# Sheet1.net
KiCad netlist of a schematic drawn in Altium Designer
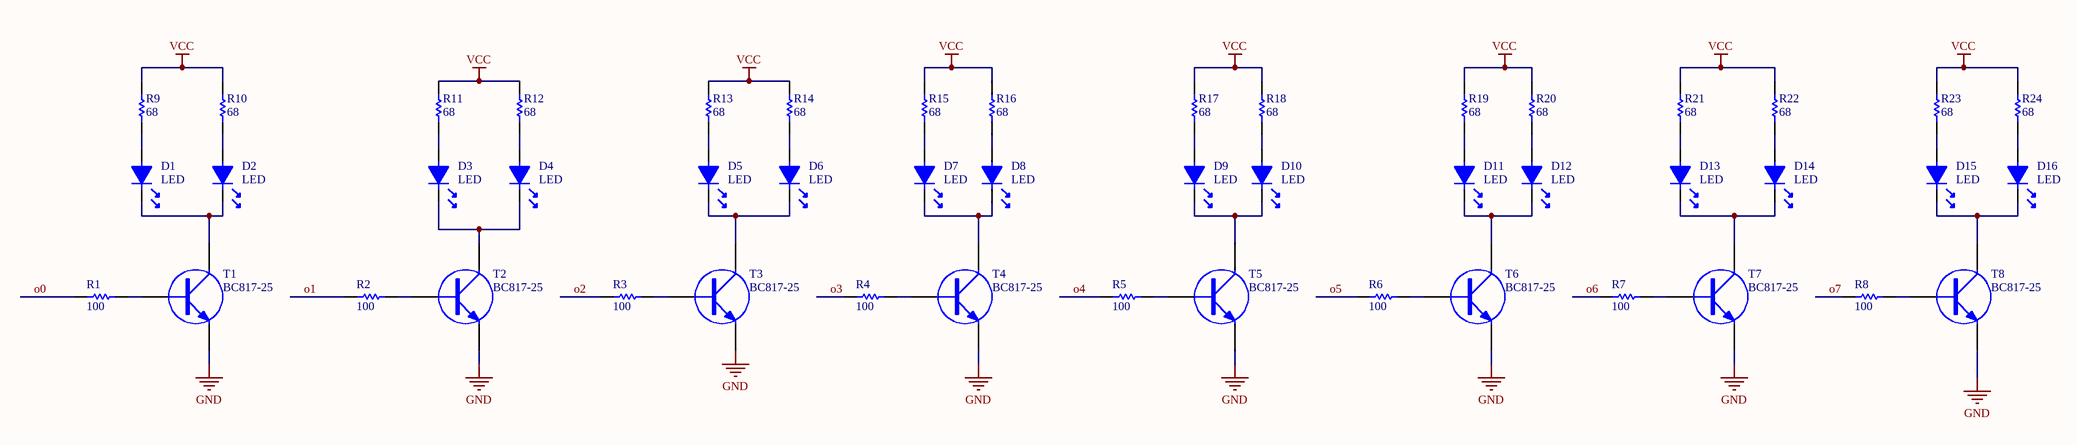
[diagram p0: Sheet1.SchDoc]

(export (version "E")
  (design (tool "Eeschema 10.0.6"))
  (components
    (comp (ref "D1") (value "LED") (footprint "*LED_OF-SMD2835Y") (libsource (lib "LIBEBAL") (part "LED")))
    (comp (ref "D2") (value "LED") (footprint "*LED_OF-SMD2835Y") (libsource (lib "LIBEBAL") (part "LED")))
    (comp (ref "D3") (value "LED") (footprint "*LED_OF-SMD2835Y") (libsource (lib "LIBEBAL") (part "LED")))
    (comp (ref "D4") (value "LED") (footprint "*LED_OF-SMD2835Y") (libsource (lib "LIBEBAL") (part "LED")))
    (comp (ref "D5") (value "LED") (footprint "*LED_OF-SMD2835Y") (libsource (lib "LIBEBAL") (part "LED")))
    (comp (ref "D6") (value "LED") (footprint "*LED_OF-SMD2835Y") (libsource (lib "LIBEBAL") (part "LED")))
    (comp (ref "D7") (value "LED") (footprint "*LED_OF-SMD2835Y") (libsource (lib "LIBEBAL") (part "LED")))
    (comp (ref "D8") (value "LED") (footprint "*LED_OF-SMD2835Y") (libsource (lib "LIBEBAL") (part "LED")))
    (comp (ref "D9") (value "LED") (footprint "*LED_OF-SMD2835Y") (libsource (lib "LIBEBAL") (part "LED")))
    (comp (ref "D10") (value "LED") (footprint "*LED_OF-SMD2835Y") (libsource (lib "LIBEBAL") (part "LED")))
    (comp (ref "D11") (value "LED") (footprint "*LED_OF-SMD2835Y") (libsource (lib "LIBEBAL") (part "LED")))
    (comp (ref "D12") (value "LED") (footprint "*LED_OF-SMD2835Y") (libsource (lib "LIBEBAL") (part "LED")))
    (comp (ref "D13") (value "LED") (footprint "*LED_OF-SMD2835Y") (libsource (lib "LIBEBAL") (part "LED")))
    (comp (ref "D14") (value "LED") (footprint "*LED_OF-SMD2835Y") (libsource (lib "LIBEBAL") (part "LED")))
    (comp (ref "D15") (value "LED") (footprint "*LED_OF-SMD2835Y") (libsource (lib "LIBEBAL") (part "LED")))
    (comp (ref "D16") (value "LED") (footprint "*LED_OF-SMD2835Y") (libsource (lib "LIBEBAL") (part "LED")))
    (comp (ref "R1") (value "100") (footprint "0805") (libsource (lib "LIBEBAL") (part "RES")))
    (comp (ref "R2") (value "100") (footprint "0805") (libsource (lib "LIBEBAL") (part "RES")))
    (comp (ref "R3") (value "100") (footprint "0805") (libsource (lib "LIBEBAL") (part "RES")))
    (comp (ref "R4") (value "100") (footprint "0805") (libsource (lib "LIBEBAL") (part "RES")))
    (comp (ref "R5") (value "100") (footprint "0805") (libsource (lib "LIBEBAL") (part "RES")))
    (comp (ref "R6") (value "100") (footprint "0805") (libsource (lib "LIBEBAL") (part "RES")))
    (comp (ref "R7") (value "100") (footprint "0805") (libsource (lib "LIBEBAL") (part "RES")))
    (comp (ref "R8") (value "100") (footprint "0805") (libsource (lib "LIBEBAL") (part "RES")))
    (comp (ref "R9") (value "68") (footprint "0805") (libsource (lib "LIBEBAL") (part "RES")))
    (comp (ref "R10") (value "68") (footprint "0805") (libsource (lib "LIBEBAL") (part "RES")))
    (comp (ref "R11") (value "68") (footprint "0805") (libsource (lib "LIBEBAL") (part "RES")))
    (comp (ref "R12") (value "68") (footprint "0805") (libsource (lib "LIBEBAL") (part "RES")))
    (comp (ref "R13") (value "68") (footprint "0805") (libsource (lib "LIBEBAL") (part "RES")))
    (comp (ref "R14") (value "68") (footprint "0805") (libsource (lib "LIBEBAL") (part "RES")))
    (comp (ref "R15") (value "68") (footprint "0805") (libsource (lib "LIBEBAL") (part "RES")))
    (comp (ref "R16") (value "68") (footprint "0805") (libsource (lib "LIBEBAL") (part "RES")))
    (comp (ref "R17") (value "68") (footprint "0805") (libsource (lib "LIBEBAL") (part "RES")))
    (comp (ref "R18") (value "68") (footprint "0805") (libsource (lib "LIBEBAL") (part "RES")))
    (comp (ref "R19") (value "68") (footprint "0805") (libsource (lib "LIBEBAL") (part "RES")))
    (comp (ref "R20") (value "68") (footprint "0805") (libsource (lib "LIBEBAL") (part "RES")))
    (comp (ref "R21") (value "68") (footprint "0805") (libsource (lib "LIBEBAL") (part "RES")))
    (comp (ref "R22") (value "68") (footprint "0805") (libsource (lib "LIBEBAL") (part "RES")))
    (comp (ref "R23") (value "68") (footprint "0805") (libsource (lib "LIBEBAL") (part "RES")))
    (comp (ref "R24") (value "68") (footprint "0805") (libsource (lib "LIBEBAL") (part "RES")))
    (comp (ref "T1")
      (value "BC817-25")
      (footprint "SOT23")
      (libsource (lib "LIBEBAL") (part "TRANSISTOR NPN"))
    )
    (comp (ref "T2")
      (value "BC817-25")
      (footprint "SOT23")
      (libsource (lib "LIBEBAL") (part "TRANSISTOR NPN"))
    )
    (comp (ref "T3")
      (value "BC817-25")
      (footprint "SOT23")
      (libsource (lib "LIBEBAL") (part "TRANSISTOR NPN"))
    )
    (comp (ref "T4")
      (value "BC817-25")
      (footprint "SOT23")
      (libsource (lib "LIBEBAL") (part "TRANSISTOR NPN"))
    )
    (comp (ref "T5")
      (value "BC817-25")
      (footprint "SOT23")
      (libsource (lib "LIBEBAL") (part "TRANSISTOR NPN"))
    )
    (comp (ref "T6")
      (value "BC817-25")
      (footprint "SOT23")
      (libsource (lib "LIBEBAL") (part "TRANSISTOR NPN"))
    )
    (comp (ref "T7")
      (value "BC817-25")
      (footprint "SOT23")
      (libsource (lib "LIBEBAL") (part "TRANSISTOR NPN"))
    )
    (comp (ref "T8")
      (value "BC817-25")
      (footprint "SOT23")
      (libsource (lib "LIBEBAL") (part "TRANSISTOR NPN"))
    )
  )
  (nets
    (net (code "1") (name "/o0") (class "Default")
      (node (ref "R1") (pin "1") (pinfunction "1_1") (pintype "passive"))
    )
    (net (code "2") (name "/o1") (class "Default")
      (node (ref "R2") (pin "1") (pinfunction "1_1") (pintype "passive"))
    )
    (net (code "3") (name "/o2") (class "Default")
      (node (ref "R3") (pin "1") (pinfunction "1_1") (pintype "passive"))
    )
    (net (code "4") (name "/o3") (class "Default")
      (node (ref "R4") (pin "1") (pinfunction "1_1") (pintype "passive"))
    )
    (net (code "5") (name "/o4") (class "Default")
      (node (ref "R5") (pin "1") (pinfunction "1_1") (pintype "passive"))
    )
    (net (code "6") (name "/o5") (class "Default")
      (node (ref "R6") (pin "1") (pinfunction "1_1") (pintype "passive"))
    )
    (net (code "7") (name "/o6") (class "Default")
      (node (ref "R7") (pin "1") (pinfunction "1_1") (pintype "passive"))
    )
    (net (code "8") (name "/o7") (class "Default")
      (node (ref "R8") (pin "1") (pinfunction "1_1") (pintype "passive"))
    )
    (net (code "9") (name "GND") (class "Default")
      (node (ref "T1") (pin "3") (pinfunction "E_3") (pintype "passive"))
      (node (ref "T2") (pin "3") (pinfunction "E_3") (pintype "passive"))
      (node (ref "T3") (pin "3") (pinfunction "E_3") (pintype "passive"))
      (node (ref "T4") (pin "3") (pinfunction "E_3") (pintype "passive"))
      (node (ref "T5") (pin "3") (pinfunction "E_3") (pintype "passive"))
      (node (ref "T6") (pin "3") (pinfunction "E_3") (pintype "passive"))
      (node (ref "T7") (pin "3") (pinfunction "E_3") (pintype "passive"))
      (node (ref "T8") (pin "3") (pinfunction "E_3") (pintype "passive"))
    )
    (net (code "10") (name "Net-(D1-Pad1)") (class "Default")
      (node (ref "D1") (pin "1") (pinfunction "1_1") (pintype "passive"))
      (node (ref "R9") (pin "1") (pinfunction "1_1") (pintype "passive"))
    )
    (net (code "11") (name "Net-(D2-Pad1)") (class "Default")
      (node (ref "D2") (pin "1") (pinfunction "1_1") (pintype "passive"))
      (node (ref "R10") (pin "1") (pinfunction "1_1") (pintype "passive"))
    )
    (net (code "12") (name "Net-(D3-Pad1)") (class "Default")
      (node (ref "D3") (pin "1") (pinfunction "1_1") (pintype "passive"))
      (node (ref "R11") (pin "1") (pinfunction "1_1") (pintype "passive"))
    )
    (net (code "13") (name "Net-(D4-Pad1)") (class "Default")
      (node (ref "D4") (pin "1") (pinfunction "1_1") (pintype "passive"))
      (node (ref "R12") (pin "1") (pinfunction "1_1") (pintype "passive"))
    )
    (net (code "14") (name "Net-(D5-Pad1)") (class "Default")
      (node (ref "D5") (pin "1") (pinfunction "1_1") (pintype "passive"))
      (node (ref "R13") (pin "1") (pinfunction "1_1") (pintype "passive"))
    )
    (net (code "15") (name "Net-(D6-Pad1)") (class "Default")
      (node (ref "D6") (pin "1") (pinfunction "1_1") (pintype "passive"))
      (node (ref "R14") (pin "1") (pinfunction "1_1") (pintype "passive"))
    )
    (net (code "16") (name "Net-(D7-Pad1)") (class "Default")
      (node (ref "D7") (pin "1") (pinfunction "1_1") (pintype "passive"))
      (node (ref "R15") (pin "1") (pinfunction "1_1") (pintype "passive"))
    )
    (net (code "17") (name "Net-(D8-Pad1)") (class "Default")
      (node (ref "D8") (pin "1") (pinfunction "1_1") (pintype "passive"))
      (node (ref "R16") (pin "1") (pinfunction "1_1") (pintype "passive"))
    )
    (net (code "18") (name "Net-(D9-Pad1)") (class "Default")
      (node (ref "D9") (pin "1") (pinfunction "1_1") (pintype "passive"))
      (node (ref "R17") (pin "1") (pinfunction "1_1") (pintype "passive"))
    )
    (net (code "19") (name "Net-(D10-Pad1)") (class "Default")
      (node (ref "D10") (pin "1") (pinfunction "1_1") (pintype "passive"))
      (node (ref "R18") (pin "1") (pinfunction "1_1") (pintype "passive"))
    )
    (net (code "20") (name "Net-(D11-Pad1)") (class "Default")
      (node (ref "D11") (pin "1") (pinfunction "1_1") (pintype "passive"))
      (node (ref "R19") (pin "1") (pinfunction "1_1") (pintype "passive"))
    )
    (net (code "21") (name "Net-(D12-Pad1)") (class "Default")
      (node (ref "D12") (pin "1") (pinfunction "1_1") (pintype "passive"))
      (node (ref "R20") (pin "1") (pinfunction "1_1") (pintype "passive"))
    )
    (net (code "22") (name "Net-(D13-Pad1)") (class "Default")
      (node (ref "D13") (pin "1") (pinfunction "1_1") (pintype "passive"))
      (node (ref "R21") (pin "1") (pinfunction "1_1") (pintype "passive"))
    )
    (net (code "23") (name "Net-(D14-Pad1)") (class "Default")
      (node (ref "D14") (pin "1") (pinfunction "1_1") (pintype "passive"))
      (node (ref "R22") (pin "1") (pinfunction "1_1") (pintype "passive"))
    )
    (net (code "24") (name "Net-(D15-Pad1)") (class "Default")
      (node (ref "D15") (pin "1") (pinfunction "1_1") (pintype "passive"))
      (node (ref "R23") (pin "1") (pinfunction "1_1") (pintype "passive"))
    )
    (net (code "25") (name "Net-(D16-Pad1)") (class "Default")
      (node (ref "D16") (pin "1") (pinfunction "1_1") (pintype "passive"))
      (node (ref "R24") (pin "1") (pinfunction "1_1") (pintype "passive"))
    )
    (net (code "26") (name "Net-(T1-B)") (class "Default")
      (node (ref "R1") (pin "2") (pinfunction "2_2") (pintype "passive"))
      (node (ref "T1") (pin "1") (pinfunction "B_1") (pintype "passive"))
    )
    (net (code "27") (name "Net-(T1-C)") (class "Default")
      (node (ref "D1") (pin "2") (pinfunction "2_2") (pintype "passive"))
      (node (ref "D2") (pin "2") (pinfunction "2_2") (pintype "passive"))
      (node (ref "T1") (pin "2") (pinfunction "C_2") (pintype "passive"))
    )
    (net (code "28") (name "Net-(T2-B)") (class "Default")
      (node (ref "R2") (pin "2") (pinfunction "2_2") (pintype "passive"))
      (node (ref "T2") (pin "1") (pinfunction "B_1") (pintype "passive"))
    )
    (net (code "29") (name "Net-(T2-C)") (class "Default")
      (node (ref "D3") (pin "2") (pinfunction "2_2") (pintype "passive"))
      (node (ref "D4") (pin "2") (pinfunction "2_2") (pintype "passive"))
      (node (ref "T2") (pin "2") (pinfunction "C_2") (pintype "passive"))
    )
    (net (code "30") (name "Net-(T3-B)") (class "Default")
      (node (ref "R3") (pin "2") (pinfunction "2_2") (pintype "passive"))
      (node (ref "T3") (pin "1") (pinfunction "B_1") (pintype "passive"))
    )
    (net (code "31") (name "Net-(T3-C)") (class "Default")
      (node (ref "D5") (pin "2") (pinfunction "2_2") (pintype "passive"))
      (node (ref "D6") (pin "2") (pinfunction "2_2") (pintype "passive"))
      (node (ref "T3") (pin "2") (pinfunction "C_2") (pintype "passive"))
    )
    (net (code "32") (name "Net-(T4-B)") (class "Default")
      (node (ref "R4") (pin "2") (pinfunction "2_2") (pintype "passive"))
      (node (ref "T4") (pin "1") (pinfunction "B_1") (pintype "passive"))
    )
    (net (code "33") (name "Net-(T4-C)") (class "Default")
      (node (ref "D7") (pin "2") (pinfunction "2_2") (pintype "passive"))
      (node (ref "D8") (pin "2") (pinfunction "2_2") (pintype "passive"))
      (node (ref "T4") (pin "2") (pinfunction "C_2") (pintype "passive"))
    )
    (net (code "34") (name "Net-(T5-B)") (class "Default")
      (node (ref "R5") (pin "2") (pinfunction "2_2") (pintype "passive"))
      (node (ref "T5") (pin "1") (pinfunction "B_1") (pintype "passive"))
    )
    (net (code "35") (name "Net-(T5-C)") (class "Default")
      (node (ref "D10") (pin "2") (pinfunction "2_2") (pintype "passive"))
      (node (ref "D9") (pin "2") (pinfunction "2_2") (pintype "passive"))
      (node (ref "T5") (pin "2") (pinfunction "C_2") (pintype "passive"))
    )
    (net (code "36") (name "Net-(T6-B)") (class "Default")
      (node (ref "R6") (pin "2") (pinfunction "2_2") (pintype "passive"))
      (node (ref "T6") (pin "1") (pinfunction "B_1") (pintype "passive"))
    )
    (net (code "37") (name "Net-(T6-C)") (class "Default")
      (node (ref "D11") (pin "2") (pinfunction "2_2") (pintype "passive"))
      (node (ref "D12") (pin "2") (pinfunction "2_2") (pintype "passive"))
      (node (ref "T6") (pin "2") (pinfunction "C_2") (pintype "passive"))
    )
    (net (code "38") (name "Net-(T7-B)") (class "Default")
      (node (ref "R7") (pin "2") (pinfunction "2_2") (pintype "passive"))
      (node (ref "T7") (pin "1") (pinfunction "B_1") (pintype "passive"))
    )
    (net (code "39") (name "Net-(T7-C)") (class "Default")
      (node (ref "D13") (pin "2") (pinfunction "2_2") (pintype "passive"))
      (node (ref "D14") (pin "2") (pinfunction "2_2") (pintype "passive"))
      (node (ref "T7") (pin "2") (pinfunction "C_2") (pintype "passive"))
    )
    (net (code "40") (name "Net-(T8-B)") (class "Default")
      (node (ref "R8") (pin "2") (pinfunction "2_2") (pintype "passive"))
      (node (ref "T8") (pin "1") (pinfunction "B_1") (pintype "passive"))
    )
    (net (code "41") (name "Net-(T8-C)") (class "Default")
      (node (ref "D15") (pin "2") (pinfunction "2_2") (pintype "passive"))
      (node (ref "D16") (pin "2") (pinfunction "2_2") (pintype "passive"))
      (node (ref "T8") (pin "2") (pinfunction "C_2") (pintype "passive"))
    )
    (net (code "42") (name "VCC") (class "Default")
      (node (ref "R10") (pin "2") (pinfunction "2_2") (pintype "passive"))
      (node (ref "R11") (pin "2") (pinfunction "2_2") (pintype "passive"))
      (node (ref "R12") (pin "2") (pinfunction "2_2") (pintype "passive"))
      (node (ref "R13") (pin "2") (pinfunction "2_2") (pintype "passive"))
      (node (ref "R14") (pin "2") (pinfunction "2_2") (pintype "passive"))
      (node (ref "R15") (pin "2") (pinfunction "2_2") (pintype "passive"))
      (node (ref "R16") (pin "2") (pinfunction "2_2") (pintype "passive"))
      (node (ref "R17") (pin "2") (pinfunction "2_2") (pintype "passive"))
      (node (ref "R18") (pin "2") (pinfunction "2_2") (pintype "passive"))
      (node (ref "R19") (pin "2") (pinfunction "2_2") (pintype "passive"))
      (node (ref "R20") (pin "2") (pinfunction "2_2") (pintype "passive"))
      (node (ref "R21") (pin "2") (pinfunction "2_2") (pintype "passive"))
      (node (ref "R22") (pin "2") (pinfunction "2_2") (pintype "passive"))
      (node (ref "R23") (pin "2") (pinfunction "2_2") (pintype "passive"))
      (node (ref "R24") (pin "2") (pinfunction "2_2") (pintype "passive"))
      (node (ref "R9") (pin "2") (pinfunction "2_2") (pintype "passive"))
    )
  )
)
